# Pi-Bus_Breakout_IO.net
KiCad netlist of a schematic drawn in EAGLE
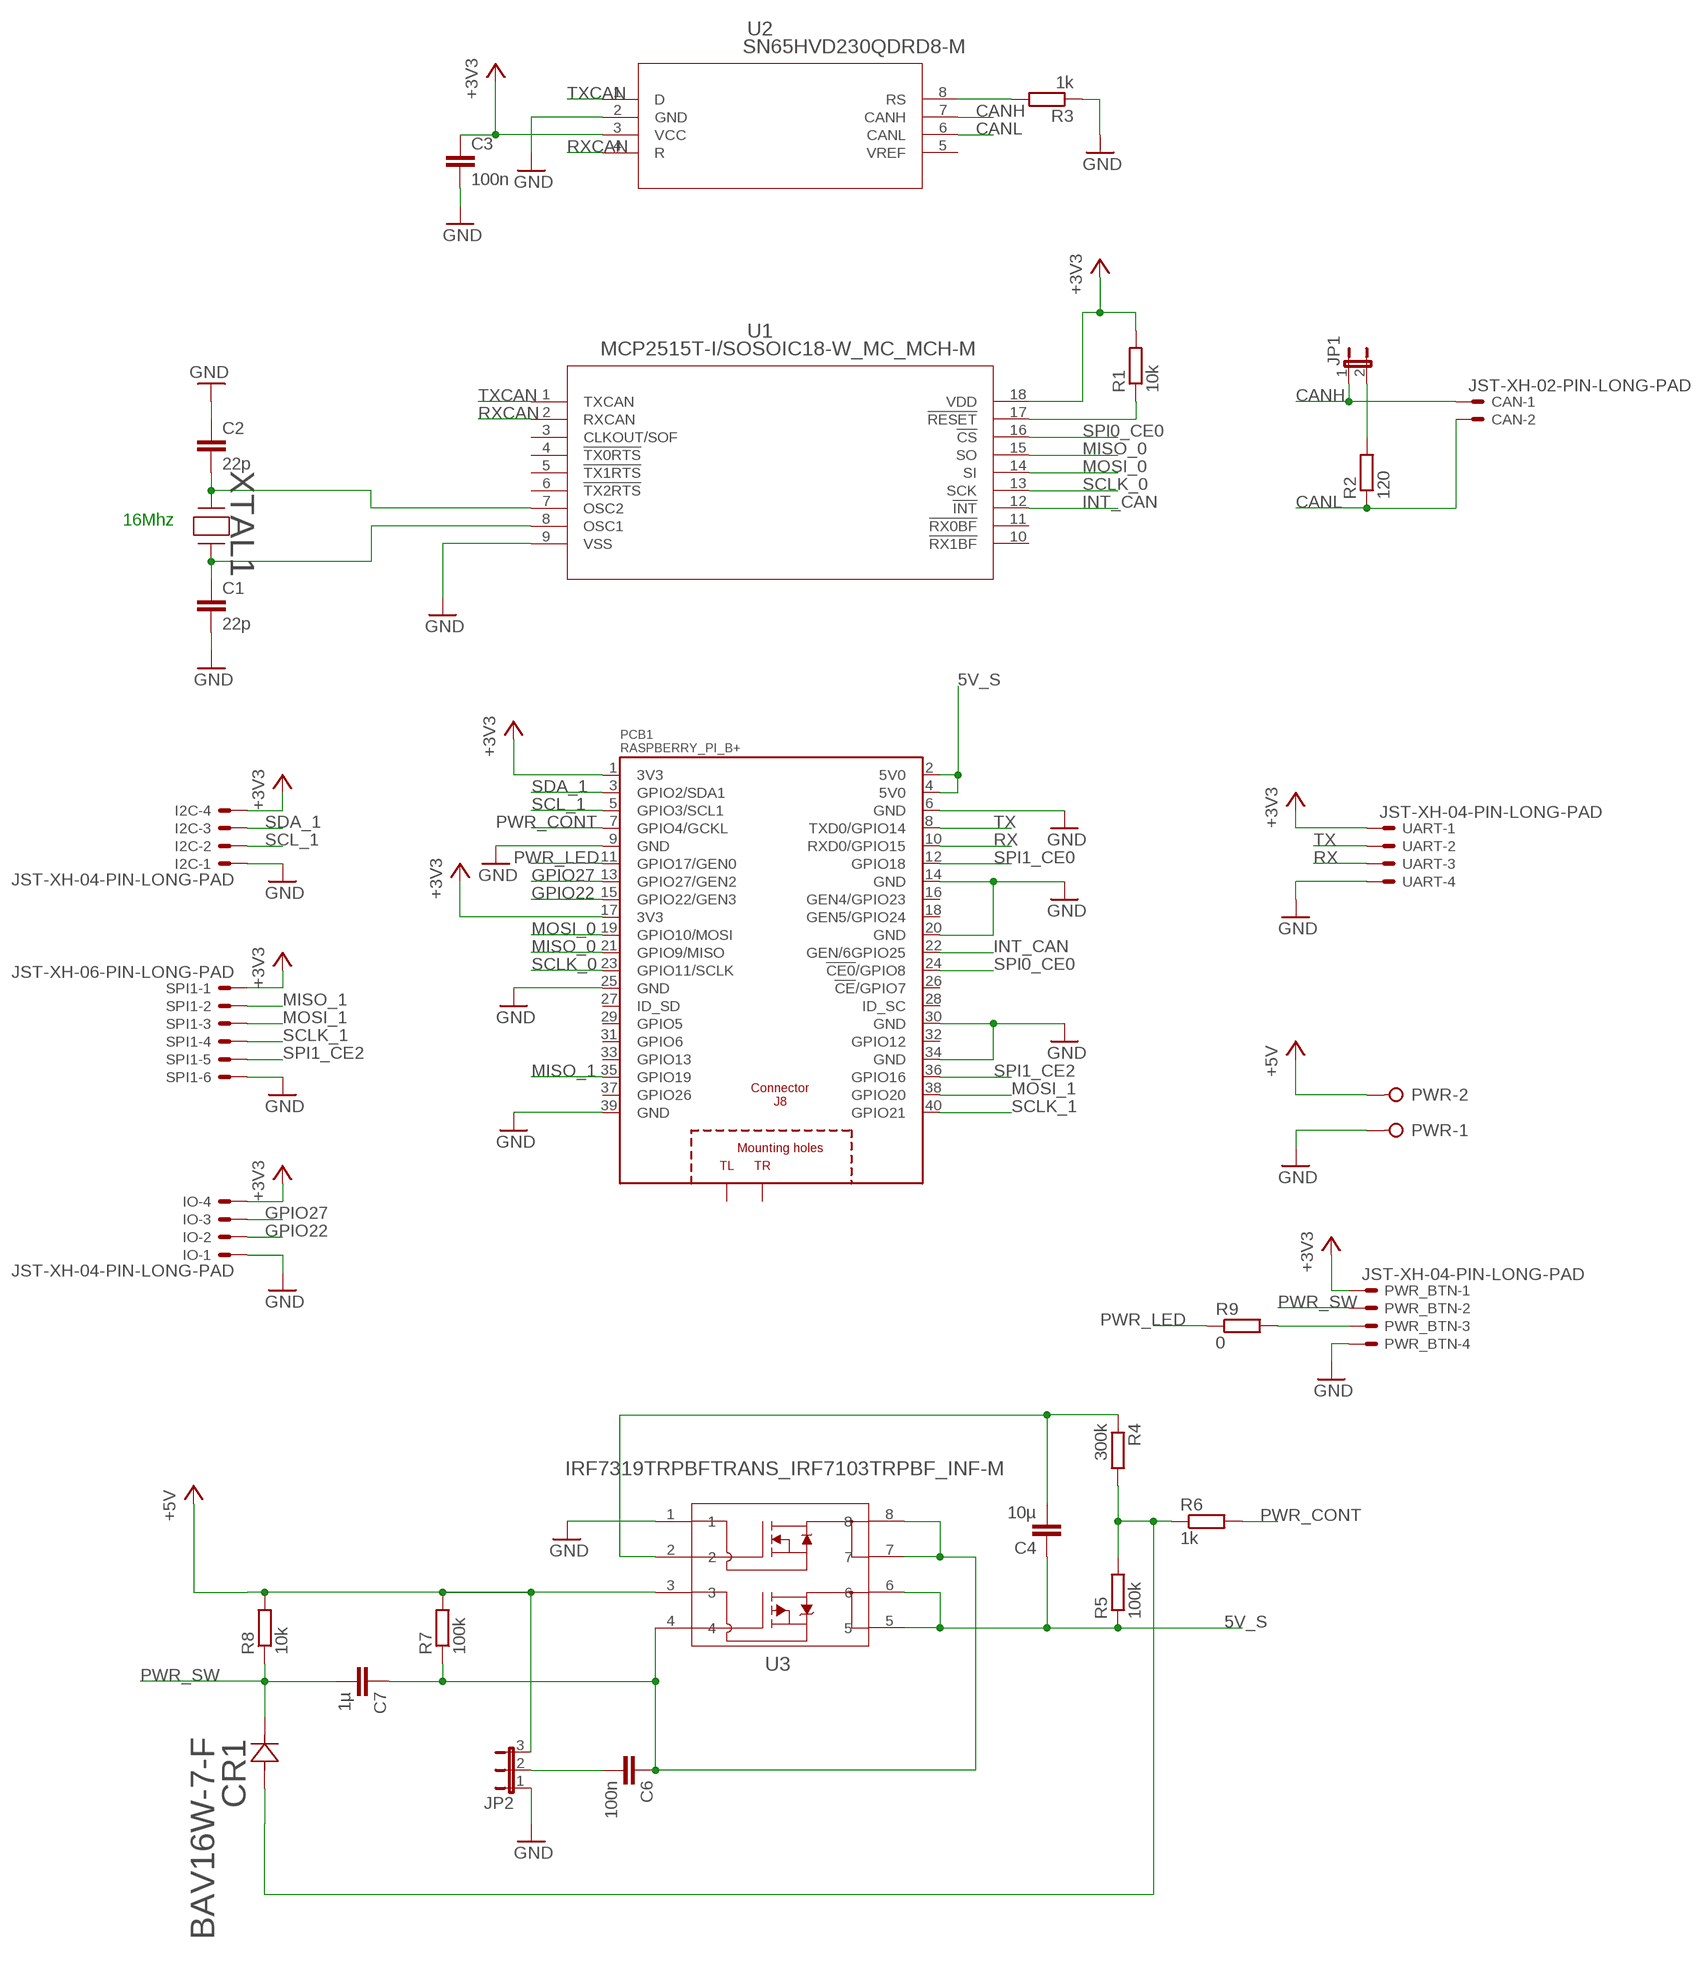
[diagram p0: schematic, sheet 1]

(export (version "E")
  (design (tool "Eeschema 10.0.6"))
  (components
    (comp (ref "C1")
      (value "22p")
      (footprint "eagle-import:C0805")
      (libsource (lib "eagle-import") (part "C-EUC0805"))
    )
    (comp (ref "C2")
      (value "22p")
      (footprint "eagle-import:C0805")
      (libsource (lib "eagle-import") (part "C-EUC0805"))
    )
    (comp (ref "C3")
      (value "100n")
      (footprint "eagle-import:C0805")
      (libsource (lib "eagle-import") (part "C-EUC0805"))
    )
    (comp (ref "C4")
      (value "10µ")
      (footprint "eagle-import:C0805")
      (libsource (lib "eagle-import") (part "C-EUC0805"))
    )
    (comp (ref "C6")
      (value "100n")
      (footprint "eagle-import:C0805")
      (libsource (lib "eagle-import") (part "C-EUC0805"))
    )
    (comp (ref "C7")
      (value "1µ")
      (footprint "eagle-import:C0805")
      (libsource (lib "eagle-import") (part "C-EUC0805"))
    )
    (comp (ref "CAN")
      (value "JST-XH-02-PIN-LONG-PAD")
      (footprint "eagle-import:JST-XH-02-PACKAGE-LONG-PAD")
      (libsource (lib "eagle-import") (part "JST-XH-02-PIN-LONG-PAD"))
    )
    (comp (ref "CR1")
      (value "BAV16W-7-F")
      (footprint "eagle-import:SOD123_DIO")
      (fields (field (name "COPYRIGHT") "Copyright (C) 2022 Ultra Librarian. All rights reserved."))
      (libsource (lib "eagle-import") (part "BAV16W-7-F"))
    )
    (comp (ref "I2C")
      (value "JST-XH-04-PIN-LONG-PAD")
      (footprint "eagle-import:JST-XH-04-PACKAGE-LONG-PAD")
      (libsource (lib "eagle-import") (part "JST-XH-04-PIN-LONG-PAD"))
    )
    (comp (ref "IO")
      (value "JST-XH-04-PIN-LONG-PAD")
      (footprint "eagle-import:JST-XH-04-PACKAGE-LONG-PAD")
      (libsource (lib "eagle-import") (part "JST-XH-04-PIN-LONG-PAD"))
    )
    (comp (ref "JP1")
      (value "JP1E")
      (footprint "eagle-import:JP1")
      (libsource (lib "eagle-import") (part "JP1E"))
    )
    (comp (ref "JP2")
      (value "JP2E")
      (footprint "eagle-import:JP2")
      (libsource (lib "eagle-import") (part "JP2E"))
    )
    (comp (ref "PCB1")
      (value "RASPBERRY_PI_B+")
      (footprint "eagle-import:RASPBERRY_PI_B+")
      (libsource (lib "eagle-import") (part "RASPBERRY_PI_B+"))
    )
    (comp (ref "PWR")
      (value "W237-02P")
      (footprint "eagle-import:W237-132")
      (libsource (lib "eagle-import") (part "W237-02P"))
    )
    (comp (ref "PWR_BTN")
      (value "JST-XH-04-PIN-LONG-PAD")
      (footprint "eagle-import:JST-XH-04-PACKAGE-LONG-PAD")
      (libsource (lib "eagle-import") (part "JST-XH-04-PIN-LONG-PAD"))
    )
    (comp (ref "R1")
      (value "10k")
      (footprint "eagle-import:R0805")
      (libsource (lib "eagle-import") (part "R-EU_R0805"))
    )
    (comp (ref "R2")
      (value "120")
      (footprint "eagle-import:R0805")
      (libsource (lib "eagle-import") (part "R-EU_R0805"))
    )
    (comp (ref "R3")
      (value "1k")
      (footprint "eagle-import:R0805")
      (libsource (lib "eagle-import") (part "R-EU_R0805"))
    )
    (comp (ref "R4")
      (value "300k")
      (footprint "eagle-import:R0805")
      (libsource (lib "eagle-import") (part "R-EU_R0805"))
    )
    (comp (ref "R5")
      (value "100k")
      (footprint "eagle-import:R0805")
      (libsource (lib "eagle-import") (part "R-EU_R0805"))
    )
    (comp (ref "R6")
      (value "1k")
      (footprint "eagle-import:R0805")
      (libsource (lib "eagle-import") (part "R-EU_R0805"))
    )
    (comp (ref "R7")
      (value "100k")
      (footprint "eagle-import:R0805")
      (libsource (lib "eagle-import") (part "R-EU_R0805"))
    )
    (comp (ref "R8")
      (value "10k")
      (footprint "eagle-import:R0805")
      (libsource (lib "eagle-import") (part "R-EU_R0805"))
    )
    (comp (ref "R9")
      (value "0")
      (footprint "eagle-import:R0805")
      (libsource (lib "eagle-import") (part "R-EU_R0805"))
    )
    (comp (ref "SPI1")
      (value "JST-XH-06-PIN-LONG-PAD")
      (footprint "eagle-import:JST-XH-06-PACKAGE-LONG-PAD")
      (libsource (lib "eagle-import") (part "JST-XH-06-PIN-LONG-PAD"))
    )
    (comp (ref "U1")
      (value "MCP2515T-I/SOSOIC18-W_MC_MCH-M")
      (footprint "eagle-import:SOIC18-W_MC_MCH-M")
      (fields
        (field (name "MANUFACTURER_PART_NUMBER") "MCP2515T-I/SO")
        (field (name "COPYRIGHT") "Copyright (C) 2022 Ultra Librarian. All rights reserved.")
      )
      (libsource (lib "eagle-import") (part "MCP2515T-I/SOSOIC18-W_MC_MCH-M"))
    )
    (comp (ref "U2")
      (value "SN65HVD230QDRD8-M")
      (footprint "eagle-import:D8-M")
      (fields
        (field (name "MANUFACTURER_PART_NUMBER") "SN65HVD230QDR")
        (field (name "COPYRIGHT") "Copyright (C) 2022 Ultra Librarian. All rights reserved.")
      )
      (libsource (lib "eagle-import") (part "SN65HVD230QDRD8-M"))
    )
    (comp (ref "U3")
      (value "IRF7319TRPBFTRANS_IRF7103TRPBF_INF-M")
      (footprint "eagle-import:TRANS_IRF7103TRPBF_INF-M")
      (fields
        (field (name "MANUFACTURER_PART_NUMBER") "IRF7319TRPBF")
        (field (name "COPYRIGHT") "Copyright (C) 2022 Ultra Librarian. All rights reserved.")
      )
      (libsource (lib "eagle-import") (part "IRF7319TRPBFTRANS_IRF7103TRPBF_INF-M"))
    )
    (comp (ref "UART")
      (value "JST-XH-04-PIN-LONG-PAD")
      (footprint "eagle-import:JST-XH-04-PACKAGE-LONG-PAD")
      (libsource (lib "eagle-import") (part "JST-XH-04-PIN-LONG-PAD"))
    )
    (comp (ref "XTAL1")
      (value "8Mhz")
      (footprint "eagle-import:XTAL_8PF_ATF_EUR")
      (fields
        (field (name "MANUFACTURER_PART_NUMBER") "16.000MHZ 49USMX/30/50/40/18PF/ATF")
        (field (name "COPYRIGHT") "Copyright (C) 2022 Ultra Librarian. All rights reserved.")
      )
      (libsource (lib "eagle-import") (part "16.000MHZ_49USMX/30/50/40/18PF"))
    )
  )
  (nets
    (net (code "1") (name "+3V3") (class "Default")
      (node (ref "C3") (pin "1") (pinfunction "1_1") (pintype "passive"))
      (node (ref "I2C") (pin "4") (pinfunction "S_4") (pintype "passive"))
      (node (ref "IO") (pin "4") (pinfunction "S_4") (pintype "passive"))
      (node (ref "PCB1") (pin "1") (pinfunction "3V3_1") (pintype "power_in"))
      (node (ref "PCB1") (pin "17") (pinfunction "3V3_17") (pintype "power_in"))
      (node (ref "PWR_BTN") (pin "1") (pinfunction "S_1") (pintype "passive"))
      (node (ref "R1") (pin "2") (pinfunction "2_2") (pintype "passive"))
      (node (ref "SPI1") (pin "1") (pinfunction "S_1") (pintype "passive"))
      (node (ref "U1") (pin "18") (pinfunction "VDD_18") (pintype "passive"))
      (node (ref "U2") (pin "3") (pinfunction "VCC_3") (pintype "power_in"))
      (node (ref "UART") (pin "1") (pinfunction "S_1") (pintype "passive"))
    )
    (net (code "2") (name "+5V") (class "Default")
      (node (ref "JP2") (pin "3") (pinfunction "3_3") (pintype "passive"))
      (node (ref "PWR") (pin "2") (pinfunction "KL_2") (pintype "passive"))
      (node (ref "R7") (pin "2") (pinfunction "2_2") (pintype "passive"))
      (node (ref "R8") (pin "2") (pinfunction "2_2") (pintype "passive"))
      (node (ref "U3") (pin "3") (pinfunction "3_3") (pintype "passive"))
    )
    (net (code "3") (name "/5V_S") (class "Default")
      (node (ref "C4") (pin "1") (pinfunction "1_1") (pintype "passive"))
      (node (ref "PCB1") (pin "2") (pinfunction "5V0_2") (pintype "power_in"))
      (node (ref "PCB1") (pin "4") (pinfunction "5V0_4") (pintype "power_in"))
      (node (ref "R5") (pin "1") (pinfunction "1_1") (pintype "passive"))
      (node (ref "U3") (pin "5") (pinfunction "5_5") (pintype "passive"))
      (node (ref "U3") (pin "6") (pinfunction "6_6") (pintype "passive"))
    )
    (net (code "4") (name "/CANH") (class "Default")
      (node (ref "CAN") (pin "1") (pinfunction "S_1") (pintype "passive"))
      (node (ref "JP1") (pin "1") (pinfunction "1_1") (pintype "passive"))
      (node (ref "U2") (pin "7") (pinfunction "CANH_7") (pintype "output"))
    )
    (net (code "5") (name "/CANL") (class "Default")
      (node (ref "CAN") (pin "2") (pinfunction "S_2") (pintype "passive"))
      (node (ref "R2") (pin "1") (pinfunction "1_1") (pintype "passive"))
      (node (ref "U2") (pin "6") (pinfunction "CANL_6") (pintype "output"))
    )
    (net (code "6") (name "/GPIO22") (class "Default")
      (node (ref "IO") (pin "2") (pinfunction "S_2") (pintype "passive"))
      (node (ref "PCB1") (pin "15") (pinfunction "GPIO22/GEN3_15") (pintype "bidirectional"))
    )
    (net (code "7") (name "/GPIO27") (class "Default")
      (node (ref "IO") (pin "3") (pinfunction "S_3") (pintype "passive"))
      (node (ref "PCB1") (pin "13") (pinfunction "GPIO27/GEN2_13") (pintype "bidirectional"))
    )
    (net (code "8") (name "/INT_CAN") (class "Default")
      (node (ref "PCB1") (pin "22") (pinfunction "GEN/6GPIO25_22") (pintype "bidirectional"))
      (node (ref "U1") (pin "12") (pinfunction "~{INT}_12") (pintype "passive"))
    )
    (net (code "9") (name "/MISO_0") (class "Default")
      (node (ref "PCB1") (pin "21") (pinfunction "GPIO9/MISO_21") (pintype "bidirectional"))
      (node (ref "U1") (pin "15") (pinfunction "SO_15") (pintype "passive"))
    )
    (net (code "10") (name "/MISO_1") (class "Default")
      (node (ref "PCB1") (pin "35") (pinfunction "GPIO19_35") (pintype "bidirectional"))
      (node (ref "SPI1") (pin "2") (pinfunction "S_2") (pintype "passive"))
    )
    (net (code "11") (name "/MOSI_0") (class "Default")
      (node (ref "PCB1") (pin "19") (pinfunction "GPIO10/MOSI_19") (pintype "bidirectional"))
      (node (ref "U1") (pin "14") (pinfunction "SI_14") (pintype "passive"))
    )
    (net (code "12") (name "/MOSI_1") (class "Default")
      (node (ref "PCB1") (pin "38") (pinfunction "GPIO20_38") (pintype "bidirectional"))
      (node (ref "SPI1") (pin "3") (pinfunction "S_3") (pintype "passive"))
    )
    (net (code "13") (name "/PWR_CONT") (class "Default")
      (node (ref "PCB1") (pin "7") (pinfunction "GPIO4/GCKL_7") (pintype "bidirectional"))
      (node (ref "R6") (pin "2") (pinfunction "2_2") (pintype "passive"))
    )
    (net (code "14") (name "/PWR_LED") (class "Default")
      (node (ref "PCB1") (pin "11") (pinfunction "GPIO17/GEN0_11") (pintype "bidirectional"))
      (node (ref "R9") (pin "1") (pinfunction "1_1") (pintype "passive"))
    )
    (net (code "15") (name "/PWR_SW") (class "Default")
      (node (ref "C7") (pin "2") (pinfunction "2_2") (pintype "passive"))
      (node (ref "CR1") (pin "1") (pinfunction "1_1") (pintype "passive"))
      (node (ref "PWR_BTN") (pin "2") (pinfunction "S_2") (pintype "passive"))
      (node (ref "R8") (pin "1") (pinfunction "1_1") (pintype "passive"))
    )
    (net (code "16") (name "/RX") (class "Default")
      (node (ref "PCB1") (pin "10") (pinfunction "RXD0/GPIO15_10") (pintype "bidirectional"))
      (node (ref "UART") (pin "3") (pinfunction "S_3") (pintype "passive"))
    )
    (net (code "17") (name "/RXCAN") (class "Default")
      (node (ref "U1") (pin "2") (pinfunction "RXCAN_2") (pintype "passive"))
      (node (ref "U2") (pin "4") (pinfunction "R_4") (pintype "input"))
    )
    (net (code "18") (name "/SCLK_0") (class "Default")
      (node (ref "PCB1") (pin "23") (pinfunction "GPIO11/SCLK_23") (pintype "bidirectional"))
      (node (ref "U1") (pin "13") (pinfunction "SCK_13") (pintype "passive"))
    )
    (net (code "19") (name "/SCLK_1") (class "Default")
      (node (ref "PCB1") (pin "40") (pinfunction "GPIO21_40") (pintype "bidirectional"))
      (node (ref "SPI1") (pin "4") (pinfunction "S_4") (pintype "passive"))
    )
    (net (code "20") (name "/SCL_1") (class "Default")
      (node (ref "I2C") (pin "2") (pinfunction "S_2") (pintype "passive"))
      (node (ref "PCB1") (pin "5") (pinfunction "GPIO3/SCL1_5") (pintype "bidirectional"))
    )
    (net (code "21") (name "/SDA_1") (class "Default")
      (node (ref "I2C") (pin "3") (pinfunction "S_3") (pintype "passive"))
      (node (ref "PCB1") (pin "3") (pinfunction "GPIO2/SDA1_3") (pintype "bidirectional"))
    )
    (net (code "22") (name "/SPI0_CE0") (class "Default")
      (node (ref "PCB1") (pin "24") (pinfunction "~{CE0}/GPIO8_24") (pintype "bidirectional"))
      (node (ref "U1") (pin "16") (pinfunction "~{CS}_16") (pintype "passive"))
    )
    (net (code "23") (name "/SPI1_CE0") (class "Default")
      (node (ref "PCB1") (pin "12") (pinfunction "GPIO18_12") (pintype "bidirectional"))
    )
    (net (code "24") (name "/SPI1_CE2") (class "Default")
      (node (ref "PCB1") (pin "36") (pinfunction "GPIO16_36") (pintype "bidirectional"))
      (node (ref "SPI1") (pin "5") (pinfunction "S_5") (pintype "passive"))
    )
    (net (code "25") (name "/TX") (class "Default")
      (node (ref "PCB1") (pin "8") (pinfunction "TXD0/GPIO14_8") (pintype "bidirectional"))
      (node (ref "UART") (pin "2") (pinfunction "S_2") (pintype "passive"))
    )
    (net (code "26") (name "/TXCAN") (class "Default")
      (node (ref "U1") (pin "1") (pinfunction "TXCAN_1") (pintype "passive"))
      (node (ref "U2") (pin "1") (pinfunction "D_1") (pintype "input"))
    )
    (net (code "27") (name "/VREF") (class "Default")
      (node (ref "U2") (pin "5") (pinfunction "VREF_5") (pintype "power_in"))
    )
    (net (code "28") (name "GND") (class "Default")
      (node (ref "C1") (pin "2") (pinfunction "2_2") (pintype "passive"))
      (node (ref "C2") (pin "1") (pinfunction "1_1") (pintype "passive"))
      (node (ref "C3") (pin "2") (pinfunction "2_2") (pintype "passive"))
      (node (ref "I2C") (pin "1") (pinfunction "S_1") (pintype "passive"))
      (node (ref "IO") (pin "1") (pinfunction "S_1") (pintype "passive"))
      (node (ref "JP2") (pin "1") (pinfunction "1_1") (pintype "passive"))
      (node (ref "PCB1") (pin "14") (pinfunction "GND_14") (pintype "power_in"))
      (node (ref "PCB1") (pin "20") (pinfunction "GND_20") (pintype "power_in"))
      (node (ref "PCB1") (pin "25") (pinfunction "GND_25") (pintype "power_in"))
      (node (ref "PCB1") (pin "30") (pinfunction "GND_30") (pintype "power_in"))
      (node (ref "PCB1") (pin "34") (pinfunction "GND_34") (pintype "power_in"))
      (node (ref "PCB1") (pin "39") (pinfunction "GND_39") (pintype "power_in"))
      (node (ref "PCB1") (pin "6") (pinfunction "GND_6") (pintype "power_in"))
      (node (ref "PCB1") (pin "9") (pinfunction "GND_9") (pintype "power_in"))
      (node (ref "PWR") (pin "1") (pinfunction "KL_1") (pintype "passive"))
      (node (ref "PWR_BTN") (pin "4") (pinfunction "S_4") (pintype "passive"))
      (node (ref "R3") (pin "1") (pinfunction "1_1") (pintype "passive"))
      (node (ref "SPI1") (pin "6") (pinfunction "S_6") (pintype "passive"))
      (node (ref "U1") (pin "9") (pinfunction "VSS_9") (pintype "passive"))
      (node (ref "U2") (pin "2") (pinfunction "GND_2") (pintype "power_in"))
      (node (ref "U3") (pin "1") (pinfunction "1_1") (pintype "passive"))
      (node (ref "UART") (pin "4") (pinfunction "S_4") (pintype "passive"))
    )
    (net (code "29") (name "Net-(C4-Pad2)") (class "Default")
      (node (ref "C4") (pin "2") (pinfunction "2_2") (pintype "passive"))
      (node (ref "R4") (pin "1") (pinfunction "1_1") (pintype "passive"))
      (node (ref "U3") (pin "2") (pinfunction "2_2") (pintype "passive"))
    )
    (net (code "30") (name "Net-(C6-Pad1)") (class "Default")
      (node (ref "C6") (pin "1") (pinfunction "1_1") (pintype "passive"))
      (node (ref "C7") (pin "1") (pinfunction "1_1") (pintype "passive"))
      (node (ref "R7") (pin "1") (pinfunction "1_1") (pintype "passive"))
      (node (ref "U3") (pin "4") (pinfunction "4_4") (pintype "passive"))
      (node (ref "U3") (pin "7") (pinfunction "7_7") (pintype "passive"))
      (node (ref "U3") (pin "8") (pinfunction "8_8") (pintype "passive"))
    )
    (net (code "31") (name "Net-(C6-Pad2)") (class "Default")
      (node (ref "C6") (pin "2") (pinfunction "2_2") (pintype "passive"))
      (node (ref "JP2") (pin "2") (pinfunction "2_2") (pintype "passive"))
    )
    (net (code "32") (name "Net-(CR1-Pad2)") (class "Default")
      (node (ref "CR1") (pin "2") (pinfunction "2_2") (pintype "passive"))
      (node (ref "R4") (pin "2") (pinfunction "2_2") (pintype "passive"))
      (node (ref "R5") (pin "2") (pinfunction "2_2") (pintype "passive"))
      (node (ref "R6") (pin "1") (pinfunction "1_1") (pintype "passive"))
    )
    (net (code "33") (name "Net-(JP1-Pad2)") (class "Default")
      (node (ref "JP1") (pin "2") (pinfunction "2_2") (pintype "passive"))
      (node (ref "R2") (pin "2") (pinfunction "2_2") (pintype "passive"))
    )
    (net (code "34") (name "Net-(PWR_BTNC-S)") (class "Default")
      (node (ref "PWR_BTN") (pin "3") (pinfunction "S_3") (pintype "passive"))
      (node (ref "R9") (pin "2") (pinfunction "2_2") (pintype "passive"))
    )
    (net (code "35") (name "Net-(U1-OSC1)") (class "Default")
      (node (ref "C1") (pin "1") (pinfunction "1_1") (pintype "passive"))
      (node (ref "U1") (pin "8") (pinfunction "OSC1_8") (pintype "passive"))
      (node (ref "XTAL1") (pin "2") (pinfunction "2_2") (pintype "passive"))
    )
    (net (code "36") (name "Net-(U1-OSC2)") (class "Default")
      (node (ref "C2") (pin "2") (pinfunction "2_2") (pintype "passive"))
      (node (ref "U1") (pin "7") (pinfunction "OSC2_7") (pintype "passive"))
      (node (ref "XTAL1") (pin "1") (pinfunction "1_1") (pintype "passive"))
    )
    (net (code "37") (name "Net-(U1-~{RESET})") (class "Default")
      (node (ref "R1") (pin "1") (pinfunction "1_1") (pintype "passive"))
      (node (ref "U1") (pin "17") (pinfunction "~{RESET}_17") (pintype "passive"))
    )
    (net (code "38") (name "Net-(U2-RS)") (class "Default")
      (node (ref "R3") (pin "2") (pinfunction "2_2") (pintype "passive"))
      (node (ref "U2") (pin "8") (pinfunction "RS_8") (pintype "input"))
    )
    (net (code "39") (name "unconnected-(PCB1-GEN4{slash}GPIO23-Pad16)") (class "Default")
      (node (ref "PCB1") (pin "16") (pinfunction "GEN4/GPIO23_16") (pintype "bidirectional"))
    )
    (net (code "40") (name "unconnected-(PCB1-GEN5{slash}GPIO24-Pad18)") (class "Default")
      (node (ref "PCB1") (pin "18") (pinfunction "GEN5/GPIO24_18") (pintype "bidirectional"))
    )
    (net (code "41") (name "unconnected-(PCB1-GPIO5-Pad29)") (class "Default")
      (node (ref "PCB1") (pin "29") (pinfunction "GPIO5_29") (pintype "bidirectional"))
    )
    (net (code "42") (name "unconnected-(PCB1-GPIO6-Pad31)") (class "Default")
      (node (ref "PCB1") (pin "31") (pinfunction "GPIO6_31") (pintype "bidirectional"))
    )
    (net (code "43") (name "unconnected-(PCB1-GPIO12-Pad32)") (class "Default")
      (node (ref "PCB1") (pin "32") (pinfunction "GPIO12_32") (pintype "bidirectional"))
    )
    (net (code "44") (name "unconnected-(PCB1-GPIO13-Pad33)") (class "Default")
      (node (ref "PCB1") (pin "33") (pinfunction "GPIO13_33") (pintype "bidirectional"))
    )
    (net (code "45") (name "unconnected-(PCB1-GPIO26-Pad37)") (class "Default")
      (node (ref "PCB1") (pin "37") (pinfunction "GPIO26_37") (pintype "bidirectional"))
    )
    (net (code "46") (name "unconnected-(PCB1-ID_SC-Pad28)") (class "Default")
      (node (ref "PCB1") (pin "28") (pinfunction "ID_SC_28") (pintype "bidirectional"))
    )
    (net (code "47") (name "unconnected-(PCB1-ID_SD-Pad27)") (class "Default")
      (node (ref "PCB1") (pin "27") (pinfunction "ID_SD_27") (pintype "bidirectional"))
    )
    (net (code "48") (name "unconnected-(PCB1-TL-PadPE_TL)") (class "Default")
      (node (ref "PCB1") (pin "PE_TL") (pinfunction "TL_PE_TL") (pintype "bidirectional"))
    )
    (net (code "49") (name "unconnected-(PCB1-TR-PadPE_TR)") (class "Default")
      (node (ref "PCB1") (pin "PE_TR") (pinfunction "TR_PE_TR") (pintype "bidirectional"))
    )
    (net (code "50") (name "unconnected-(PCB1-~{CE}{slash}GPIO7-Pad26)") (class "Default")
      (node (ref "PCB1") (pin "26") (pinfunction "~{CE}/GPIO7_26") (pintype "bidirectional"))
    )
    (net (code "51") (name "unconnected-(U1-CLKOUT{slash}SOF-Pad3)") (class "Default")
      (node (ref "U1") (pin "3") (pinfunction "CLKOUT/SOF_3") (pintype "passive"))
    )
    (net (code "52") (name "unconnected-(U1-~{RX0BF}-Pad11)") (class "Default")
      (node (ref "U1") (pin "11") (pinfunction "~{RX0BF}_11") (pintype "passive"))
    )
    (net (code "53") (name "unconnected-(U1-~{RX1BF}-Pad10)") (class "Default")
      (node (ref "U1") (pin "10") (pinfunction "~{RX1BF}_10") (pintype "passive"))
    )
    (net (code "54") (name "unconnected-(U1-~{TX0RTS}-Pad4)") (class "Default")
      (node (ref "U1") (pin "4") (pinfunction "~{TX0RTS}_4") (pintype "passive"))
    )
    (net (code "55") (name "unconnected-(U1-~{TX1RTS}-Pad5)") (class "Default")
      (node (ref "U1") (pin "5") (pinfunction "~{TX1RTS}_5") (pintype "passive"))
    )
    (net (code "56") (name "unconnected-(U1-~{TX2RTS}-Pad6)") (class "Default")
      (node (ref "U1") (pin "6") (pinfunction "~{TX2RTS}_6") (pintype "passive"))
    )
  )
)
